# wm8960.net
KiCad netlist of a schematic drawn in Altium Designer
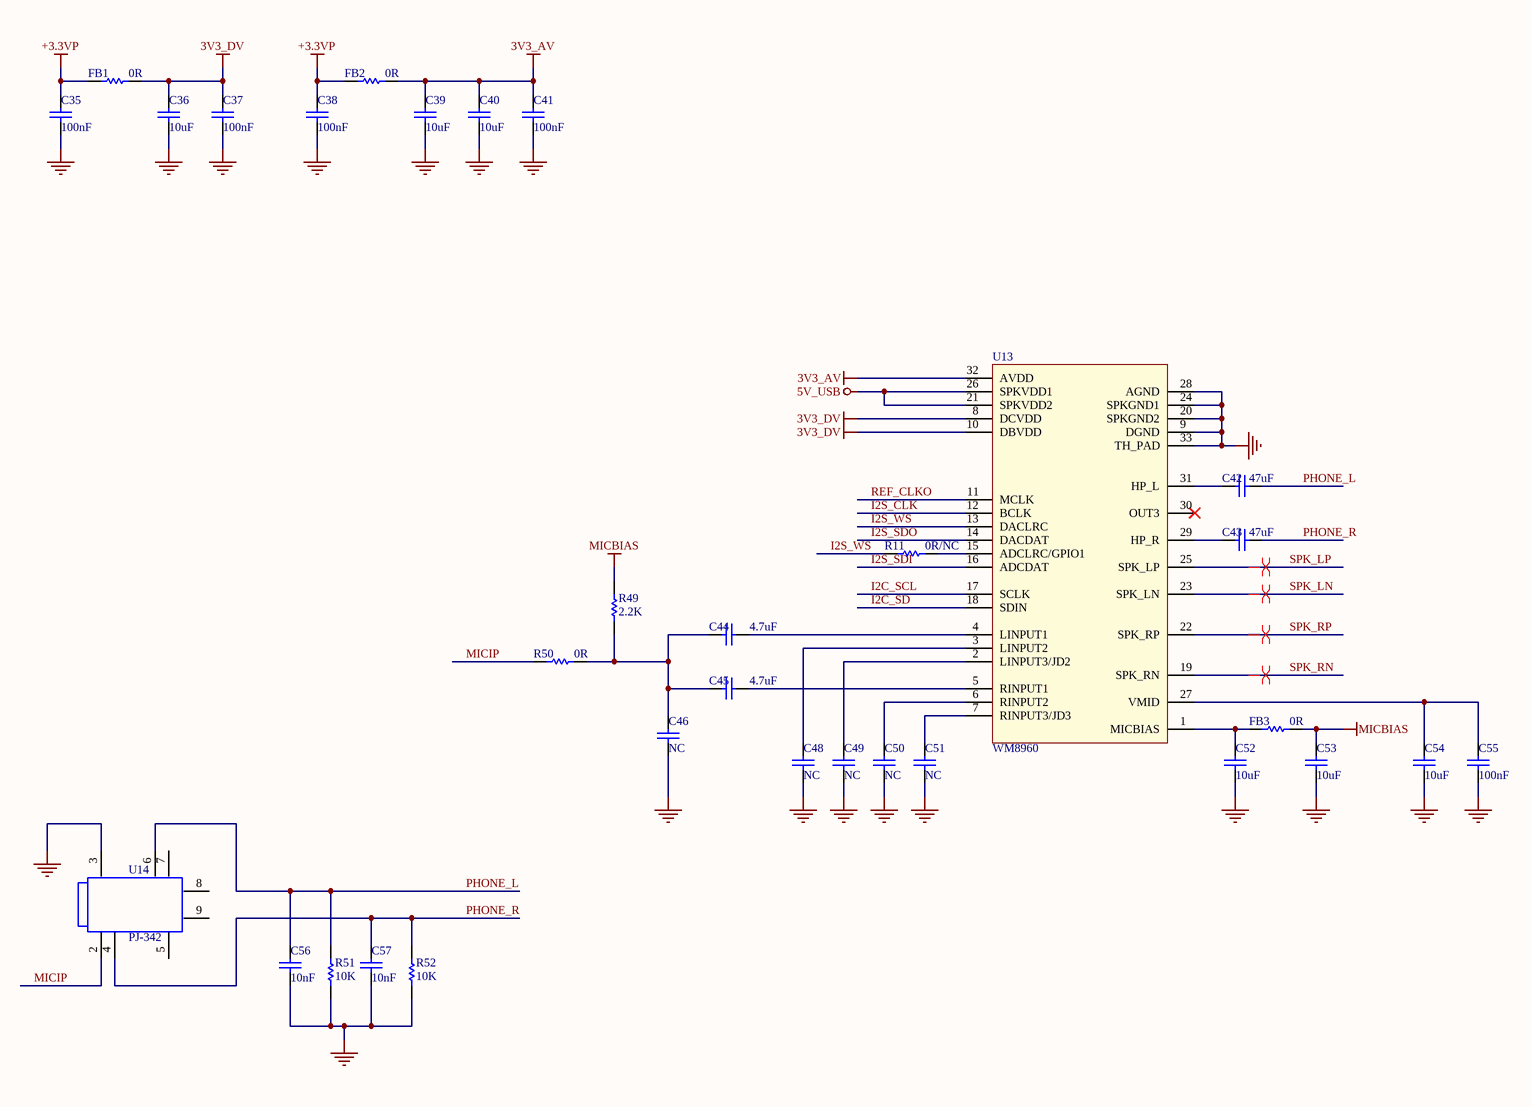
[diagram p0: wm8960.SchDoc]

(export (version "E")
  (design (tool "Eeschema 10.0.6"))
  (components
    (comp (ref "C35")
      (value "100nF")
      (footprint "C0603L")
      (description "Capacitor (Semiconductor SIM Model)")
      (fields (field (name "Comment") "Cap Semi") (field (name "PUBLISHER") "Altium Limited"))
      (libsource (lib "Miscellaneous Devices") (part "Cap Semi"))
    )
    (comp (ref "C36")
      (value "10uF")
      (footprint "C0603L")
      (description "Capacitor (Semiconductor SIM Model)")
      (fields (field (name "Comment") "Cap Semi") (field (name "PUBLISHER") "Altium Limited"))
      (libsource (lib "Miscellaneous Devices") (part "Cap Semi"))
    )
    (comp (ref "C37")
      (value "100nF")
      (footprint "C0603L")
      (description "Capacitor (Semiconductor SIM Model)")
      (fields (field (name "Comment") "Cap Semi") (field (name "PUBLISHER") "Altium Limited"))
      (libsource (lib "Miscellaneous Devices") (part "Cap Semi"))
    )
    (comp (ref "C38")
      (value "100nF")
      (footprint "C0603L")
      (description "Capacitor (Semiconductor SIM Model)")
      (fields (field (name "Comment") "Cap Semi") (field (name "PUBLISHER") "Altium Limited"))
      (libsource (lib "Miscellaneous Devices") (part "Cap Semi"))
    )
    (comp (ref "C39")
      (value "10uF")
      (footprint "C0603L")
      (description "Capacitor (Semiconductor SIM Model)")
      (fields (field (name "Comment") "Cap Semi") (field (name "PUBLISHER") "Altium Limited"))
      (libsource (lib "Miscellaneous Devices") (part "Cap Semi"))
    )
    (comp (ref "C40")
      (value "10uF")
      (footprint "C0603L")
      (description "Capacitor (Semiconductor SIM Model)")
      (fields (field (name "Comment") "Cap Semi") (field (name "PUBLISHER") "Altium Limited"))
      (libsource (lib "Miscellaneous Devices") (part "Cap Semi"))
    )
    (comp (ref "C41")
      (value "100nF")
      (footprint "C0603L")
      (description "Capacitor (Semiconductor SIM Model)")
      (fields (field (name "Comment") "Cap Semi") (field (name "PUBLISHER") "Altium Limited"))
      (libsource (lib "Miscellaneous Devices") (part "Cap Semi"))
    )
    (comp (ref "C42")
      (value "47uF")
      (footprint "C0805L")
      (description "Capacitor (Semiconductor SIM Model)")
      (fields (field (name "Comment") "Cap Semi") (field (name "PUBLISHER") "Altium Limited"))
      (libsource (lib "Miscellaneous Devices") (part "Cap Semi"))
    )
    (comp (ref "C43")
      (value "47uF")
      (footprint "C0805L")
      (description "Capacitor (Semiconductor SIM Model)")
      (fields (field (name "Comment") "Cap Semi") (field (name "PUBLISHER") "Altium Limited"))
      (libsource (lib "Miscellaneous Devices") (part "Cap Semi"))
    )
    (comp (ref "C44")
      (value "4.7uF")
      (footprint "C0603L")
      (description "Capacitor (Semiconductor SIM Model)")
      (fields (field (name "Comment") "Cap Semi") (field (name "PUBLISHER") "Altium Limited"))
      (libsource (lib "Miscellaneous Devices") (part "Cap Semi"))
    )
    (comp (ref "C45")
      (value "4.7uF")
      (footprint "C0603L")
      (description "Capacitor (Semiconductor SIM Model)")
      (fields (field (name "Comment") "Cap Semi") (field (name "PUBLISHER") "Altium Limited"))
      (libsource (lib "Miscellaneous Devices") (part "Cap Semi"))
    )
    (comp (ref "C46")
      (value "NC")
      (footprint "C0603L")
      (description "Capacitor (Semiconductor SIM Model)")
      (fields (field (name "Comment") "Cap Semi") (field (name "PUBLISHER") "Altium Limited"))
      (libsource (lib "Miscellaneous Devices") (part "Cap Semi"))
    )
    (comp (ref "C48")
      (value "NC")
      (footprint "C0603L")
      (description "Capacitor (Semiconductor SIM Model)")
      (fields (field (name "Comment") "Cap Semi") (field (name "PUBLISHER") "Altium Limited"))
      (libsource (lib "Miscellaneous Devices") (part "Cap Semi"))
    )
    (comp (ref "C49")
      (value "NC")
      (footprint "C0603L")
      (description "Capacitor (Semiconductor SIM Model)")
      (fields (field (name "Comment") "Cap Semi") (field (name "PUBLISHER") "Altium Limited"))
      (libsource (lib "Miscellaneous Devices") (part "Cap Semi"))
    )
    (comp (ref "C50")
      (value "NC")
      (footprint "C0603L")
      (description "Capacitor (Semiconductor SIM Model)")
      (fields (field (name "Comment") "Cap Semi") (field (name "PUBLISHER") "Altium Limited"))
      (libsource (lib "Miscellaneous Devices") (part "Cap Semi"))
    )
    (comp (ref "C51")
      (value "NC")
      (footprint "C0603L")
      (description "Capacitor (Semiconductor SIM Model)")
      (fields (field (name "Comment") "Cap Semi") (field (name "PUBLISHER") "Altium Limited"))
      (libsource (lib "Miscellaneous Devices") (part "Cap Semi"))
    )
    (comp (ref "C52")
      (value "10uF")
      (footprint "C0603L")
      (description "Capacitor (Semiconductor SIM Model)")
      (fields (field (name "Comment") "Cap Semi") (field (name "PUBLISHER") "Altium Limited"))
      (libsource (lib "Miscellaneous Devices") (part "Cap Semi"))
    )
    (comp (ref "C53")
      (value "10uF")
      (footprint "C0603L")
      (description "Capacitor (Semiconductor SIM Model)")
      (fields (field (name "Comment") "Cap Semi") (field (name "PUBLISHER") "Altium Limited"))
      (libsource (lib "Miscellaneous Devices") (part "Cap Semi"))
    )
    (comp (ref "C54")
      (value "10uF")
      (footprint "C0603L")
      (description "Capacitor (Semiconductor SIM Model)")
      (fields (field (name "Comment") "Cap Semi") (field (name "PUBLISHER") "Altium Limited"))
      (libsource (lib "Miscellaneous Devices") (part "Cap Semi"))
    )
    (comp (ref "C55")
      (value "100nF")
      (footprint "C0603L")
      (description "Capacitor (Semiconductor SIM Model)")
      (fields (field (name "Comment") "Cap Semi") (field (name "PUBLISHER") "Altium Limited"))
      (libsource (lib "Miscellaneous Devices") (part "Cap Semi"))
    )
    (comp (ref "C56")
      (value "10nF")
      (footprint "C0603L")
      (description "Capacitor (Semiconductor SIM Model)")
      (fields (field (name "Comment") "Cap Semi") (field (name "PUBLISHER") "Altium Limited"))
      (libsource (lib "Miscellaneous Devices") (part "Cap Semi"))
    )
    (comp (ref "C57")
      (value "10nF")
      (footprint "C0603L")
      (description "Capacitor (Semiconductor SIM Model)")
      (fields (field (name "Comment") "Cap Semi") (field (name "PUBLISHER") "Altium Limited"))
      (libsource (lib "Miscellaneous Devices") (part "Cap Semi"))
    )
    (comp (ref "FB1")
      (value "0R")
      (footprint "R0603L")
      (description "Semiconductor Resistor")
      (fields (field (name "Comment") "Res Semi") (field (name "PUBLISHER") "Altium Limited"))
      (libsource (lib "Miscellaneous Devices") (part "Res Semi"))
    )
    (comp (ref "FB2")
      (value "0R")
      (footprint "R0603L")
      (description "Semiconductor Resistor")
      (fields (field (name "Comment") "Res Semi") (field (name "PUBLISHER") "Altium Limited"))
      (libsource (lib "Miscellaneous Devices") (part "Res Semi"))
    )
    (comp (ref "FB3")
      (value "0R")
      (footprint "R0603L")
      (description "Semiconductor Resistor")
      (fields (field (name "Comment") "Res Semi") (field (name "PUBLISHER") "Altium Limited"))
      (libsource (lib "Miscellaneous Devices") (part "Res Semi"))
    )
    (comp (ref "R11")
      (value "0R/NC")
      (footprint "R0603L")
      (description "Semiconductor Resistor")
      (fields (field (name "Comment") "Res Semi") (field (name "PUBLISHER") "Altium Limited"))
      (libsource (lib "Miscellaneous Devices") (part "Res Semi"))
    )
    (comp (ref "R49")
      (value "2.2K")
      (footprint "R0603L")
      (description "Semiconductor Resistor")
      (fields (field (name "Comment") "Res Semi") (field (name "PUBLISHER") "Altium Limited"))
      (libsource (lib "Miscellaneous Devices") (part "Res Semi"))
    )
    (comp (ref "R50")
      (value "0R")
      (footprint "R0603L")
      (description "Semiconductor Resistor")
      (fields (field (name "Comment") "Res Semi") (field (name "PUBLISHER") "Altium Limited"))
      (libsource (lib "Miscellaneous Devices") (part "Res Semi"))
    )
    (comp (ref "R51")
      (value "10K")
      (footprint "R0603L")
      (description "Semiconductor Resistor")
      (fields (field (name "Comment") "Res Semi") (field (name "PUBLISHER") "Altium Limited"))
      (libsource (lib "Miscellaneous Devices") (part "Res Semi"))
    )
    (comp (ref "R52")
      (value "10K")
      (footprint "R0603L")
      (description "Semiconductor Resistor")
      (fields (field (name "Comment") "Res Semi") (field (name "PUBLISHER") "Altium Limited"))
      (libsource (lib "Miscellaneous Devices") (part "Res Semi"))
    )
    (comp (ref "U13") (value "WM8960") (footprint "QFN_32") (libsource (lib "Schlib1") (part "WM8960")))
    (comp (ref "U14")
      (value "PJ-342")
      (footprint "PJ-342_PCB")
      (libsource (lib "wooya_lib_footprint") (part "PJ-342"))
    )
  )
  (nets
    (net (code "1") (name "+3.3VP") (class "Default")
      (node (ref "C35") (pin "1") (pinfunction "1_1") (pintype "passive"))
      (node (ref "C38") (pin "1") (pinfunction "1_1") (pintype "passive"))
      (node (ref "FB1") (pin "2") (pinfunction "2_2") (pintype "passive"))
      (node (ref "FB2") (pin "2") (pinfunction "2_2") (pintype "passive"))
    )
    (net (code "2") (name "/I2C_SCL") (class "Default")
      (node (ref "U13") (pin "17") (pinfunction "SCLK_17") (pintype "passive"))
    )
    (net (code "3") (name "/I2C_SD") (class "Default")
      (node (ref "U13") (pin "18") (pinfunction "SDIN_18") (pintype "passive"))
    )
    (net (code "4") (name "/I2S_CLK") (class "Default")
      (node (ref "U13") (pin "12") (pinfunction "BCLK_12") (pintype "passive"))
    )
    (net (code "5") (name "/I2S_SDI") (class "Default")
      (node (ref "U13") (pin "16") (pinfunction "ADCDAT_16") (pintype "passive"))
    )
    (net (code "6") (name "/I2S_SDO") (class "Default")
      (node (ref "U13") (pin "14") (pinfunction "DACDAT_14") (pintype "passive"))
    )
    (net (code "7") (name "/I2S_WS") (class "Default")
      (node (ref "R11") (pin "2") (pinfunction "2_2") (pintype "passive"))
      (node (ref "U13") (pin "13") (pinfunction "DACLRC_13") (pintype "passive"))
    )
    (net (code "8") (name "/MICIP") (class "Default")
      (node (ref "R50") (pin "2") (pinfunction "2_2") (pintype "passive"))
      (node (ref "U14") (pin "2") (pintype "passive"))
    )
    (net (code "9") (name "/PHONE_L") (class "Default")
      (node (ref "C42") (pin "2") (pinfunction "2_2") (pintype "passive"))
      (node (ref "C56") (pin "2") (pinfunction "2_2") (pintype "passive"))
      (node (ref "R51") (pin "1") (pinfunction "1_1") (pintype "passive"))
      (node (ref "U14") (pin "6") (pintype "passive"))
    )
    (net (code "10") (name "/PHONE_R") (class "Default")
      (node (ref "C43") (pin "2") (pinfunction "2_2") (pintype "passive"))
      (node (ref "C57") (pin "2") (pinfunction "2_2") (pintype "passive"))
      (node (ref "R52") (pin "1") (pinfunction "1_1") (pintype "passive"))
      (node (ref "U14") (pin "4") (pintype "passive"))
    )
    (net (code "11") (name "/REF_CLKO") (class "Default")
      (node (ref "U13") (pin "11") (pinfunction "MCLK_11") (pintype "passive"))
    )
    (net (code "12") (name "/SPK_LN") (class "Default")
      (node (ref "U13") (pin "23") (pinfunction "SPK_LN_23") (pintype "passive"))
    )
    (net (code "13") (name "/SPK_LP") (class "Default")
      (node (ref "U13") (pin "25") (pinfunction "SPK_LP_25") (pintype "passive"))
    )
    (net (code "14") (name "/SPK_RN") (class "Default")
      (node (ref "U13") (pin "19") (pinfunction "SPK_RN_19") (pintype "passive"))
    )
    (net (code "15") (name "/SPK_RP") (class "Default")
      (node (ref "U13") (pin "22") (pinfunction "SPK_RP_22") (pintype "passive"))
    )
    (net (code "16") (name "3V3_AV") (class "Default")
      (node (ref "C39") (pin "1") (pinfunction "1_1") (pintype "passive"))
      (node (ref "C40") (pin "1") (pinfunction "1_1") (pintype "passive"))
      (node (ref "C41") (pin "1") (pinfunction "1_1") (pintype "passive"))
      (node (ref "FB2") (pin "1") (pinfunction "1_1") (pintype "passive"))
      (node (ref "U13") (pin "32") (pinfunction "AVDD_32") (pintype "passive"))
    )
    (net (code "17") (name "3V3_DV") (class "Default")
      (node (ref "C36") (pin "1") (pinfunction "1_1") (pintype "passive"))
      (node (ref "C37") (pin "1") (pinfunction "1_1") (pintype "passive"))
      (node (ref "FB1") (pin "1") (pinfunction "1_1") (pintype "passive"))
      (node (ref "U13") (pin "10") (pinfunction "DBVDD_10") (pintype "passive"))
      (node (ref "U13") (pin "8") (pinfunction "DCVDD_8") (pintype "passive"))
    )
    (net (code "18") (name "5V_USB") (class "Default")
      (node (ref "U13") (pin "21") (pinfunction "SPKVDD2_21") (pintype "passive"))
      (node (ref "U13") (pin "26") (pinfunction "SPKVDD1_26") (pintype "passive"))
    )
    (net (code "19") (name "GND") (class "Default")
      (node (ref "C35") (pin "2") (pinfunction "2_2") (pintype "passive"))
      (node (ref "C36") (pin "2") (pinfunction "2_2") (pintype "passive"))
      (node (ref "C37") (pin "2") (pinfunction "2_2") (pintype "passive"))
      (node (ref "C38") (pin "2") (pinfunction "2_2") (pintype "passive"))
      (node (ref "C39") (pin "2") (pinfunction "2_2") (pintype "passive"))
      (node (ref "C40") (pin "2") (pinfunction "2_2") (pintype "passive"))
      (node (ref "C41") (pin "2") (pinfunction "2_2") (pintype "passive"))
      (node (ref "C46") (pin "2") (pinfunction "2_2") (pintype "passive"))
      (node (ref "C48") (pin "2") (pinfunction "2_2") (pintype "passive"))
      (node (ref "C49") (pin "2") (pinfunction "2_2") (pintype "passive"))
      (node (ref "C50") (pin "2") (pinfunction "2_2") (pintype "passive"))
      (node (ref "C51") (pin "2") (pinfunction "2_2") (pintype "passive"))
      (node (ref "C52") (pin "2") (pinfunction "2_2") (pintype "passive"))
      (node (ref "C53") (pin "2") (pinfunction "2_2") (pintype "passive"))
      (node (ref "C54") (pin "2") (pinfunction "2_2") (pintype "passive"))
      (node (ref "C55") (pin "2") (pinfunction "2_2") (pintype "passive"))
      (node (ref "C56") (pin "1") (pinfunction "1_1") (pintype "passive"))
      (node (ref "C57") (pin "1") (pinfunction "1_1") (pintype "passive"))
      (node (ref "R51") (pin "2") (pinfunction "2_2") (pintype "passive"))
      (node (ref "R52") (pin "2") (pinfunction "2_2") (pintype "passive"))
      (node (ref "U13") (pin "20") (pinfunction "SPKGND2_20") (pintype "passive"))
      (node (ref "U13") (pin "24") (pinfunction "SPKGND1_24") (pintype "passive"))
      (node (ref "U13") (pin "28") (pinfunction "AGND_28") (pintype "passive"))
      (node (ref "U13") (pin "33") (pinfunction "TH_PAD_33") (pintype "passive"))
      (node (ref "U13") (pin "9") (pinfunction "DGND_9") (pintype "passive"))
      (node (ref "U14") (pin "3") (pintype "passive"))
    )
    (net (code "20") (name "MICBIAS") (class "Default")
      (node (ref "C53") (pin "1") (pinfunction "1_1") (pintype "passive"))
      (node (ref "FB3") (pin "1") (pinfunction "1_1") (pintype "passive"))
      (node (ref "R49") (pin "1") (pinfunction "1_1") (pintype "passive"))
    )
    (net (code "21") (name "Net-(C44-Pad1)") (class "Default")
      (node (ref "C44") (pin "1") (pinfunction "1_1") (pintype "passive"))
      (node (ref "C45") (pin "1") (pinfunction "1_1") (pintype "passive"))
      (node (ref "C46") (pin "1") (pinfunction "1_1") (pintype "passive"))
      (node (ref "R49") (pin "2") (pinfunction "2_2") (pintype "passive"))
      (node (ref "R50") (pin "1") (pinfunction "1_1") (pintype "passive"))
    )
    (net (code "22") (name "Net-(U13-ADCLRC{slash}GPIO1)") (class "Default")
      (node (ref "R11") (pin "1") (pinfunction "1_1") (pintype "passive"))
      (node (ref "U13") (pin "15") (pinfunction "ADCLRC/GPIO1_15") (pintype "passive"))
    )
    (net (code "23") (name "Net-(U13-HP_L)") (class "Default")
      (node (ref "C42") (pin "1") (pinfunction "1_1") (pintype "passive"))
      (node (ref "U13") (pin "31") (pinfunction "HP_L_31") (pintype "passive"))
    )
    (net (code "24") (name "Net-(U13-HP_R)") (class "Default")
      (node (ref "C43") (pin "1") (pinfunction "1_1") (pintype "passive"))
      (node (ref "U13") (pin "29") (pinfunction "HP_R_29") (pintype "passive"))
    )
    (net (code "25") (name "Net-(U13-LINPUT1)") (class "Default")
      (node (ref "C44") (pin "2") (pinfunction "2_2") (pintype "passive"))
      (node (ref "U13") (pin "4") (pinfunction "LINPUT1_4") (pintype "passive"))
    )
    (net (code "26") (name "Net-(U13-LINPUT2)") (class "Default")
      (node (ref "C48") (pin "1") (pinfunction "1_1") (pintype "passive"))
      (node (ref "U13") (pin "3") (pinfunction "LINPUT2_3") (pintype "passive"))
    )
    (net (code "27") (name "Net-(U13-LINPUT3{slash}JD2)") (class "Default")
      (node (ref "C49") (pin "1") (pinfunction "1_1") (pintype "passive"))
      (node (ref "U13") (pin "2") (pinfunction "LINPUT3/JD2_2") (pintype "passive"))
    )
    (net (code "28") (name "Net-(U13-MICBIAS)") (class "Default")
      (node (ref "C52") (pin "1") (pinfunction "1_1") (pintype "passive"))
      (node (ref "FB3") (pin "2") (pinfunction "2_2") (pintype "passive"))
      (node (ref "U13") (pin "1") (pinfunction "MICBIAS_1") (pintype "passive"))
    )
    (net (code "29") (name "Net-(U13-RINPUT1)") (class "Default")
      (node (ref "C45") (pin "2") (pinfunction "2_2") (pintype "passive"))
      (node (ref "U13") (pin "5") (pinfunction "RINPUT1_5") (pintype "passive"))
    )
    (net (code "30") (name "Net-(U13-RINPUT2)") (class "Default")
      (node (ref "C50") (pin "1") (pinfunction "1_1") (pintype "passive"))
      (node (ref "U13") (pin "6") (pinfunction "RINPUT2_6") (pintype "passive"))
    )
    (net (code "31") (name "Net-(U13-RINPUT3{slash}JD3)") (class "Default")
      (node (ref "C51") (pin "1") (pinfunction "1_1") (pintype "passive"))
      (node (ref "U13") (pin "7") (pinfunction "RINPUT3/JD3_7") (pintype "passive"))
    )
    (net (code "32") (name "Net-(U13-VMID)") (class "Default")
      (node (ref "C54") (pin "1") (pinfunction "1_1") (pintype "passive"))
      (node (ref "C55") (pin "1") (pinfunction "1_1") (pintype "passive"))
      (node (ref "U13") (pin "27") (pinfunction "VMID_27") (pintype "passive"))
    )
    (net (code "33") (name "unconnected-(U13-OUT3-Pad30)") (class "Default")
      (node (ref "U13") (pin "30") (pinfunction "OUT3_30") (pintype "passive+no_connect"))
    )
    (net (code "34") (name "unconnected-(U14-Pad5)") (class "Default")
      (node (ref "U14") (pin "5") (pintype "passive"))
    )
    (net (code "35") (name "unconnected-(U14-Pad7)") (class "Default")
      (node (ref "U14") (pin "7") (pintype "passive"))
    )
    (net (code "36") (name "unconnected-(U14-Pad8)") (class "Default")
      (node (ref "U14") (pin "8") (pintype "passive"))
    )
    (net (code "37") (name "unconnected-(U14-Pad9)") (class "Default")
      (node (ref "U14") (pin "9") (pintype "passive"))
    )
  )
)
